# Swith_Matrix.net
KiCad netlist of a schematic drawn in Altium Designer
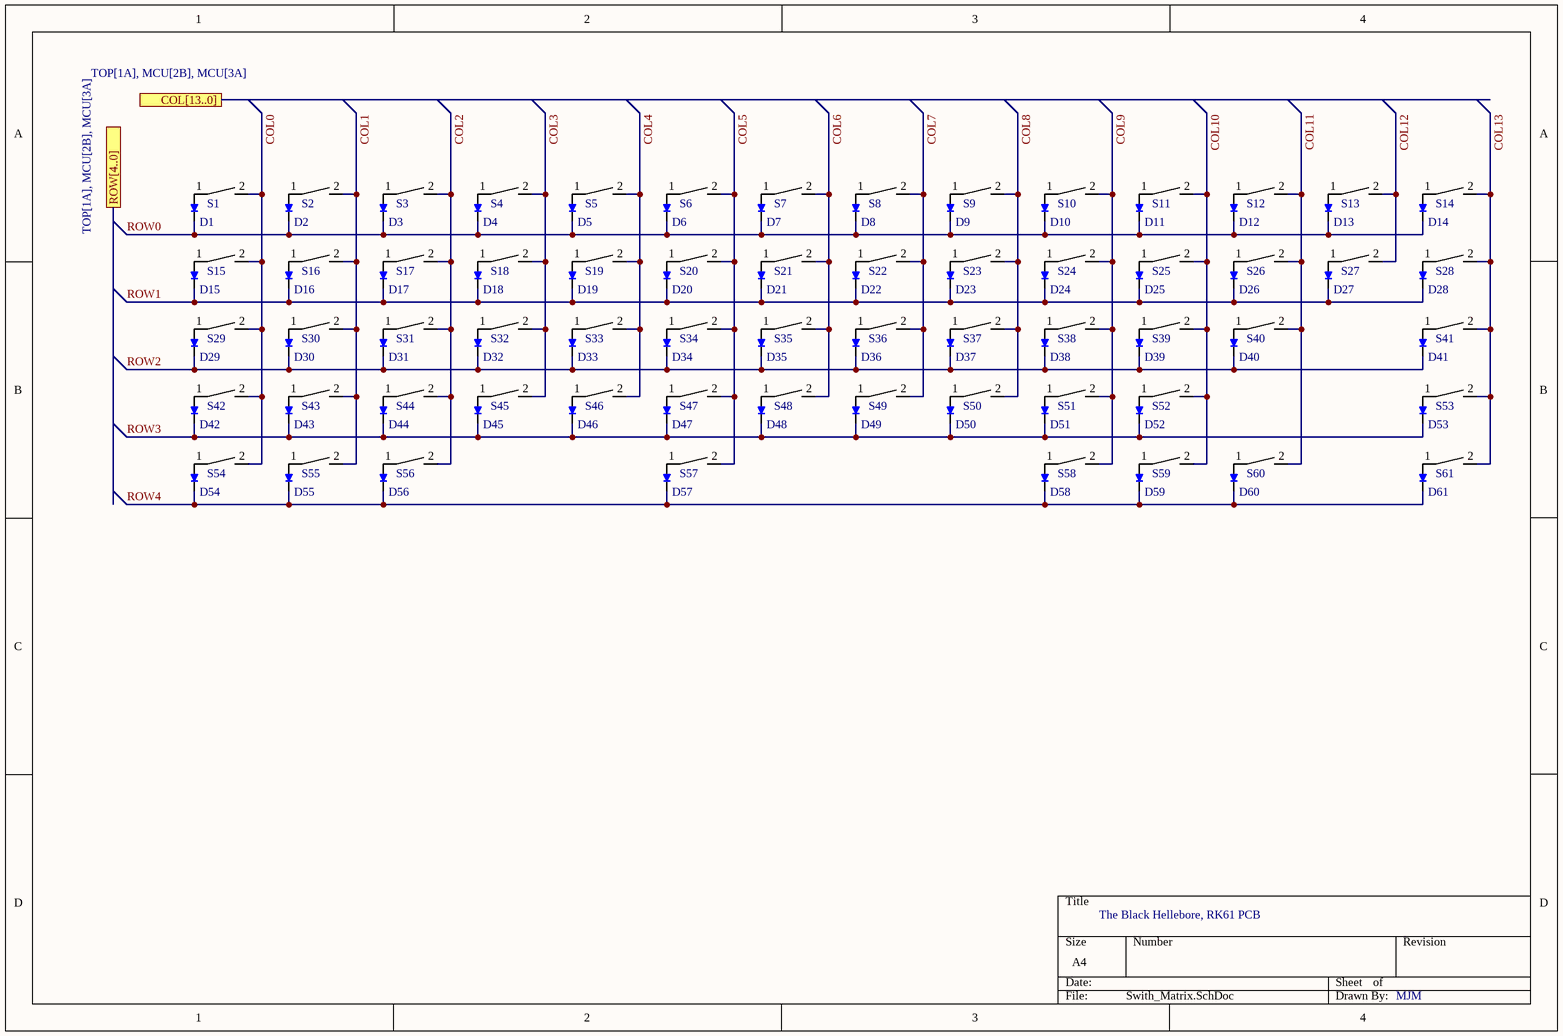
[diagram p0: Swith_Matrix.SchDoc]

(export (version "E")
  (design (tool "Eeschema 10.0.6"))
  (components
    (comp (ref "D1")
      (value "RB520S30T5G")
      (footprint "ONSC-SOD-523-2-502-01_V")
      (description "RB520S30T5G - 30 V 200 mA Surface Mount Schottky Diode - SOD-523")
      (libsource (lib "Microcom Corporation") (part "ONSC-D-K1A2-2"))
    )
    (comp (ref "D2")
      (value "RB520S30T5G")
      (footprint "ONSC-SOD-523-2-502-01_V")
      (description "RB520S30T5G - 30 V 200 mA Surface Mount Schottky Diode - SOD-523")
      (libsource (lib "Microcom Corporation") (part "ONSC-D-K1A2-2"))
    )
    (comp (ref "D3")
      (value "RB520S30T5G")
      (footprint "ONSC-SOD-523-2-502-01_V")
      (description "RB520S30T5G - 30 V 200 mA Surface Mount Schottky Diode - SOD-523")
      (libsource (lib "Microcom Corporation") (part "ONSC-D-K1A2-2"))
    )
    (comp (ref "D4")
      (value "RB520S30T5G")
      (footprint "ONSC-SOD-523-2-502-01_V")
      (description "RB520S30T5G - 30 V 200 mA Surface Mount Schottky Diode - SOD-523")
      (libsource (lib "Microcom Corporation") (part "ONSC-D-K1A2-2"))
    )
    (comp (ref "D5")
      (value "RB520S30T5G")
      (footprint "ONSC-SOD-523-2-502-01_V")
      (description "RB520S30T5G - 30 V 200 mA Surface Mount Schottky Diode - SOD-523")
      (libsource (lib "Microcom Corporation") (part "ONSC-D-K1A2-2"))
    )
    (comp (ref "D6")
      (value "RB520S30T5G")
      (footprint "ONSC-SOD-523-2-502-01_V")
      (description "RB520S30T5G - 30 V 200 mA Surface Mount Schottky Diode - SOD-523")
      (libsource (lib "Microcom Corporation") (part "ONSC-D-K1A2-2"))
    )
    (comp (ref "D7")
      (value "RB520S30T5G")
      (footprint "ONSC-SOD-523-2-502-01_V")
      (description "RB520S30T5G - 30 V 200 mA Surface Mount Schottky Diode - SOD-523")
      (libsource (lib "Microcom Corporation") (part "ONSC-D-K1A2-2"))
    )
    (comp (ref "D8")
      (value "RB520S30T5G")
      (footprint "ONSC-SOD-523-2-502-01_V")
      (description "RB520S30T5G - 30 V 200 mA Surface Mount Schottky Diode - SOD-523")
      (libsource (lib "Microcom Corporation") (part "ONSC-D-K1A2-2"))
    )
    (comp (ref "D9")
      (value "RB520S30T5G")
      (footprint "ONSC-SOD-523-2-502-01_V")
      (description "RB520S30T5G - 30 V 200 mA Surface Mount Schottky Diode - SOD-523")
      (libsource (lib "Microcom Corporation") (part "ONSC-D-K1A2-2"))
    )
    (comp (ref "D10")
      (value "RB520S30T5G")
      (footprint "ONSC-SOD-523-2-502-01_V")
      (description "RB520S30T5G - 30 V 200 mA Surface Mount Schottky Diode - SOD-523")
      (libsource (lib "Microcom Corporation") (part "ONSC-D-K1A2-2"))
    )
    (comp (ref "D11")
      (value "RB520S30T5G")
      (footprint "ONSC-SOD-523-2-502-01_V")
      (description "RB520S30T5G - 30 V 200 mA Surface Mount Schottky Diode - SOD-523")
      (libsource (lib "Microcom Corporation") (part "ONSC-D-K1A2-2"))
    )
    (comp (ref "D12")
      (value "RB520S30T5G")
      (footprint "ONSC-SOD-523-2-502-01_V")
      (description "RB520S30T5G - 30 V 200 mA Surface Mount Schottky Diode - SOD-523")
      (libsource (lib "Microcom Corporation") (part "ONSC-D-K1A2-2"))
    )
    (comp (ref "D13")
      (value "RB520S30T5G")
      (footprint "ONSC-SOD-523-2-502-01_V")
      (description "RB520S30T5G - 30 V 200 mA Surface Mount Schottky Diode - SOD-523")
      (libsource (lib "Microcom Corporation") (part "ONSC-D-K1A2-2"))
    )
    (comp (ref "D14")
      (value "RB520S30T5G")
      (footprint "ONSC-SOD-523-2-502-01_V")
      (description "RB520S30T5G - 30 V 200 mA Surface Mount Schottky Diode - SOD-523")
      (libsource (lib "Microcom Corporation") (part "ONSC-D-K1A2-2"))
    )
    (comp (ref "D15")
      (value "RB520S30T5G")
      (footprint "ONSC-SOD-523-2-502-01_V")
      (description "RB520S30T5G - 30 V 200 mA Surface Mount Schottky Diode - SOD-523")
      (libsource (lib "Microcom Corporation") (part "ONSC-D-K1A2-2"))
    )
    (comp (ref "D16")
      (value "RB520S30T5G")
      (footprint "ONSC-SOD-523-2-502-01_V")
      (description "RB520S30T5G - 30 V 200 mA Surface Mount Schottky Diode - SOD-523")
      (libsource (lib "Microcom Corporation") (part "ONSC-D-K1A2-2"))
    )
    (comp (ref "D17")
      (value "RB520S30T5G")
      (footprint "ONSC-SOD-523-2-502-01_V")
      (description "RB520S30T5G - 30 V 200 mA Surface Mount Schottky Diode - SOD-523")
      (libsource (lib "Microcom Corporation") (part "ONSC-D-K1A2-2"))
    )
    (comp (ref "D18")
      (value "RB520S30T5G")
      (footprint "ONSC-SOD-523-2-502-01_V")
      (description "RB520S30T5G - 30 V 200 mA Surface Mount Schottky Diode - SOD-523")
      (libsource (lib "Microcom Corporation") (part "ONSC-D-K1A2-2"))
    )
    (comp (ref "D19")
      (value "RB520S30T5G")
      (footprint "ONSC-SOD-523-2-502-01_V")
      (description "RB520S30T5G - 30 V 200 mA Surface Mount Schottky Diode - SOD-523")
      (libsource (lib "Microcom Corporation") (part "ONSC-D-K1A2-2"))
    )
    (comp (ref "D20")
      (value "RB520S30T5G")
      (footprint "ONSC-SOD-523-2-502-01_V")
      (description "RB520S30T5G - 30 V 200 mA Surface Mount Schottky Diode - SOD-523")
      (libsource (lib "Microcom Corporation") (part "ONSC-D-K1A2-2"))
    )
    (comp (ref "D21")
      (value "RB520S30T5G")
      (footprint "ONSC-SOD-523-2-502-01_V")
      (description "RB520S30T5G - 30 V 200 mA Surface Mount Schottky Diode - SOD-523")
      (libsource (lib "Microcom Corporation") (part "ONSC-D-K1A2-2"))
    )
    (comp (ref "D22")
      (value "RB520S30T5G")
      (footprint "ONSC-SOD-523-2-502-01_V")
      (description "RB520S30T5G - 30 V 200 mA Surface Mount Schottky Diode - SOD-523")
      (libsource (lib "Microcom Corporation") (part "ONSC-D-K1A2-2"))
    )
    (comp (ref "D23")
      (value "RB520S30T5G")
      (footprint "ONSC-SOD-523-2-502-01_V")
      (description "RB520S30T5G - 30 V 200 mA Surface Mount Schottky Diode - SOD-523")
      (libsource (lib "Microcom Corporation") (part "ONSC-D-K1A2-2"))
    )
    (comp (ref "D24")
      (value "RB520S30T5G")
      (footprint "ONSC-SOD-523-2-502-01_V")
      (description "RB520S30T5G - 30 V 200 mA Surface Mount Schottky Diode - SOD-523")
      (libsource (lib "Microcom Corporation") (part "ONSC-D-K1A2-2"))
    )
    (comp (ref "D25")
      (value "RB520S30T5G")
      (footprint "ONSC-SOD-523-2-502-01_V")
      (description "RB520S30T5G - 30 V 200 mA Surface Mount Schottky Diode - SOD-523")
      (libsource (lib "Microcom Corporation") (part "ONSC-D-K1A2-2"))
    )
    (comp (ref "D26")
      (value "RB520S30T5G")
      (footprint "ONSC-SOD-523-2-502-01_V")
      (description "RB520S30T5G - 30 V 200 mA Surface Mount Schottky Diode - SOD-523")
      (libsource (lib "Microcom Corporation") (part "ONSC-D-K1A2-2"))
    )
    (comp (ref "D27")
      (value "RB520S30T5G")
      (footprint "ONSC-SOD-523-2-502-01_V")
      (description "RB520S30T5G - 30 V 200 mA Surface Mount Schottky Diode - SOD-523")
      (libsource (lib "Microcom Corporation") (part "ONSC-D-K1A2-2"))
    )
    (comp (ref "D28")
      (value "RB520S30T5G")
      (footprint "ONSC-SOD-523-2-502-01_V")
      (description "RB520S30T5G - 30 V 200 mA Surface Mount Schottky Diode - SOD-523")
      (libsource (lib "Microcom Corporation") (part "ONSC-D-K1A2-2"))
    )
    (comp (ref "D29")
      (value "RB520S30T5G")
      (footprint "ONSC-SOD-523-2-502-01_V")
      (description "RB520S30T5G - 30 V 200 mA Surface Mount Schottky Diode - SOD-523")
      (libsource (lib "Microcom Corporation") (part "ONSC-D-K1A2-2"))
    )
    (comp (ref "D30")
      (value "RB520S30T5G")
      (footprint "ONSC-SOD-523-2-502-01_V")
      (description "RB520S30T5G - 30 V 200 mA Surface Mount Schottky Diode - SOD-523")
      (libsource (lib "Microcom Corporation") (part "ONSC-D-K1A2-2"))
    )
    (comp (ref "D31")
      (value "RB520S30T5G")
      (footprint "ONSC-SOD-523-2-502-01_V")
      (description "RB520S30T5G - 30 V 200 mA Surface Mount Schottky Diode - SOD-523")
      (libsource (lib "Microcom Corporation") (part "ONSC-D-K1A2-2"))
    )
    (comp (ref "D32")
      (value "RB520S30T5G")
      (footprint "ONSC-SOD-523-2-502-01_V")
      (description "RB520S30T5G - 30 V 200 mA Surface Mount Schottky Diode - SOD-523")
      (libsource (lib "Microcom Corporation") (part "ONSC-D-K1A2-2"))
    )
    (comp (ref "D33")
      (value "RB520S30T5G")
      (footprint "ONSC-SOD-523-2-502-01_V")
      (description "RB520S30T5G - 30 V 200 mA Surface Mount Schottky Diode - SOD-523")
      (libsource (lib "Microcom Corporation") (part "ONSC-D-K1A2-2"))
    )
    (comp (ref "D34")
      (value "RB520S30T5G")
      (footprint "ONSC-SOD-523-2-502-01_V")
      (description "RB520S30T5G - 30 V 200 mA Surface Mount Schottky Diode - SOD-523")
      (libsource (lib "Microcom Corporation") (part "ONSC-D-K1A2-2"))
    )
    (comp (ref "D35")
      (value "RB520S30T5G")
      (footprint "ONSC-SOD-523-2-502-01_V")
      (description "RB520S30T5G - 30 V 200 mA Surface Mount Schottky Diode - SOD-523")
      (libsource (lib "Microcom Corporation") (part "ONSC-D-K1A2-2"))
    )
    (comp (ref "D36")
      (value "RB520S30T5G")
      (footprint "ONSC-SOD-523-2-502-01_V")
      (description "RB520S30T5G - 30 V 200 mA Surface Mount Schottky Diode - SOD-523")
      (libsource (lib "Microcom Corporation") (part "ONSC-D-K1A2-2"))
    )
    (comp (ref "D37")
      (value "RB520S30T5G")
      (footprint "ONSC-SOD-523-2-502-01_V")
      (description "RB520S30T5G - 30 V 200 mA Surface Mount Schottky Diode - SOD-523")
      (libsource (lib "Microcom Corporation") (part "ONSC-D-K1A2-2"))
    )
    (comp (ref "D38")
      (value "RB520S30T5G")
      (footprint "ONSC-SOD-523-2-502-01_V")
      (description "RB520S30T5G - 30 V 200 mA Surface Mount Schottky Diode - SOD-523")
      (libsource (lib "Microcom Corporation") (part "ONSC-D-K1A2-2"))
    )
    (comp (ref "D39")
      (value "RB520S30T5G")
      (footprint "ONSC-SOD-523-2-502-01_V")
      (description "RB520S30T5G - 30 V 200 mA Surface Mount Schottky Diode - SOD-523")
      (libsource (lib "Microcom Corporation") (part "ONSC-D-K1A2-2"))
    )
    (comp (ref "D40")
      (value "RB520S30T5G")
      (footprint "ONSC-SOD-523-2-502-01_V")
      (description "RB520S30T5G - 30 V 200 mA Surface Mount Schottky Diode - SOD-523")
      (libsource (lib "Microcom Corporation") (part "ONSC-D-K1A2-2"))
    )
    (comp (ref "D41")
      (value "RB520S30T5G")
      (footprint "ONSC-SOD-523-2-502-01_V")
      (description "RB520S30T5G - 30 V 200 mA Surface Mount Schottky Diode - SOD-523")
      (libsource (lib "Microcom Corporation") (part "ONSC-D-K1A2-2"))
    )
    (comp (ref "D42")
      (value "RB520S30T5G")
      (footprint "ONSC-SOD-523-2-502-01_V")
      (description "RB520S30T5G - 30 V 200 mA Surface Mount Schottky Diode - SOD-523")
      (libsource (lib "Microcom Corporation") (part "ONSC-D-K1A2-2"))
    )
    (comp (ref "D43")
      (value "RB520S30T5G")
      (footprint "ONSC-SOD-523-2-502-01_V")
      (description "RB520S30T5G - 30 V 200 mA Surface Mount Schottky Diode - SOD-523")
      (libsource (lib "Microcom Corporation") (part "ONSC-D-K1A2-2"))
    )
    (comp (ref "D44")
      (value "RB520S30T5G")
      (footprint "ONSC-SOD-523-2-502-01_V")
      (description "RB520S30T5G - 30 V 200 mA Surface Mount Schottky Diode - SOD-523")
      (libsource (lib "Microcom Corporation") (part "ONSC-D-K1A2-2"))
    )
    (comp (ref "D45")
      (value "RB520S30T5G")
      (footprint "ONSC-SOD-523-2-502-01_V")
      (description "RB520S30T5G - 30 V 200 mA Surface Mount Schottky Diode - SOD-523")
      (libsource (lib "Microcom Corporation") (part "ONSC-D-K1A2-2"))
    )
    (comp (ref "D46")
      (value "RB520S30T5G")
      (footprint "ONSC-SOD-523-2-502-01_V")
      (description "RB520S30T5G - 30 V 200 mA Surface Mount Schottky Diode - SOD-523")
      (libsource (lib "Microcom Corporation") (part "ONSC-D-K1A2-2"))
    )
    (comp (ref "D47")
      (value "RB520S30T5G")
      (footprint "ONSC-SOD-523-2-502-01_V")
      (description "RB520S30T5G - 30 V 200 mA Surface Mount Schottky Diode - SOD-523")
      (libsource (lib "Microcom Corporation") (part "ONSC-D-K1A2-2"))
    )
    (comp (ref "D48")
      (value "RB520S30T5G")
      (footprint "ONSC-SOD-523-2-502-01_V")
      (description "RB520S30T5G - 30 V 200 mA Surface Mount Schottky Diode - SOD-523")
      (libsource (lib "Microcom Corporation") (part "ONSC-D-K1A2-2"))
    )
    (comp (ref "D49")
      (value "RB520S30T5G")
      (footprint "ONSC-SOD-523-2-502-01_V")
      (description "RB520S30T5G - 30 V 200 mA Surface Mount Schottky Diode - SOD-523")
      (libsource (lib "Microcom Corporation") (part "ONSC-D-K1A2-2"))
    )
    (comp (ref "D50")
      (value "RB520S30T5G")
      (footprint "ONSC-SOD-523-2-502-01_V")
      (description "RB520S30T5G - 30 V 200 mA Surface Mount Schottky Diode - SOD-523")
      (libsource (lib "Microcom Corporation") (part "ONSC-D-K1A2-2"))
    )
    (comp (ref "D51")
      (value "RB520S30T5G")
      (footprint "ONSC-SOD-523-2-502-01_V")
      (description "RB520S30T5G - 30 V 200 mA Surface Mount Schottky Diode - SOD-523")
      (libsource (lib "Microcom Corporation") (part "ONSC-D-K1A2-2"))
    )
    (comp (ref "D52")
      (value "RB520S30T5G")
      (footprint "ONSC-SOD-523-2-502-01_V")
      (description "RB520S30T5G - 30 V 200 mA Surface Mount Schottky Diode - SOD-523")
      (libsource (lib "Microcom Corporation") (part "ONSC-D-K1A2-2"))
    )
    (comp (ref "D53")
      (value "RB520S30T5G")
      (footprint "ONSC-SOD-523-2-502-01_V")
      (description "RB520S30T5G - 30 V 200 mA Surface Mount Schottky Diode - SOD-523")
      (libsource (lib "Microcom Corporation") (part "ONSC-D-K1A2-2"))
    )
    (comp (ref "D54")
      (value "RB520S30T5G")
      (footprint "ONSC-SOD-523-2-502-01_V")
      (description "RB520S30T5G - 30 V 200 mA Surface Mount Schottky Diode - SOD-523")
      (libsource (lib "Microcom Corporation") (part "ONSC-D-K1A2-2"))
    )
    (comp (ref "D55")
      (value "RB520S30T5G")
      (footprint "ONSC-SOD-523-2-502-01_V")
      (description "RB520S30T5G - 30 V 200 mA Surface Mount Schottky Diode - SOD-523")
      (libsource (lib "Microcom Corporation") (part "ONSC-D-K1A2-2"))
    )
    (comp (ref "D56")
      (value "RB520S30T5G")
      (footprint "ONSC-SOD-523-2-502-01_V")
      (description "RB520S30T5G - 30 V 200 mA Surface Mount Schottky Diode - SOD-523")
      (libsource (lib "Microcom Corporation") (part "ONSC-D-K1A2-2"))
    )
    (comp (ref "D57")
      (value "RB520S30T5G")
      (footprint "ONSC-SOD-523-2-502-01_V")
      (description "RB520S30T5G - 30 V 200 mA Surface Mount Schottky Diode - SOD-523")
      (libsource (lib "Microcom Corporation") (part "ONSC-D-K1A2-2"))
    )
    (comp (ref "D58")
      (value "RB520S30T5G")
      (footprint "ONSC-SOD-523-2-502-01_V")
      (description "RB520S30T5G - 30 V 200 mA Surface Mount Schottky Diode - SOD-523")
      (libsource (lib "Microcom Corporation") (part "ONSC-D-K1A2-2"))
    )
    (comp (ref "D59")
      (value "RB520S30T5G")
      (footprint "ONSC-SOD-523-2-502-01_V")
      (description "RB520S30T5G - 30 V 200 mA Surface Mount Schottky Diode - SOD-523")
      (libsource (lib "Microcom Corporation") (part "ONSC-D-K1A2-2"))
    )
    (comp (ref "D60")
      (value "RB520S30T5G")
      (footprint "ONSC-SOD-523-2-502-01_V")
      (description "RB520S30T5G - 30 V 200 mA Surface Mount Schottky Diode - SOD-523")
      (libsource (lib "Microcom Corporation") (part "ONSC-D-K1A2-2"))
    )
    (comp (ref "D61")
      (value "RB520S30T5G")
      (footprint "ONSC-SOD-523-2-502-01_V")
      (description "RB520S30T5G - 30 V 200 mA Surface Mount Schottky Diode - SOD-523")
      (libsource (lib "Microcom Corporation") (part "ONSC-D-K1A2-2"))
    )
    (comp (ref "S1")
      (value "1U-5Pin")
      (footprint "SW_PG151101S11")
      (description "Keyswitch 1U Cherry MX, 5Pin, CPG151101S11-16")
      (fields (field (name "MF") "Kailh") (field (name "MP") "CPG151101S11-16"))
      (libsource (lib "Microcom Corporation") (part "PG151101S11"))
    )
    (comp (ref "S2")
      (value "1U-5Pin")
      (footprint "SW_PG151101S11")
      (description "Keyswitch 1U Cherry MX, 5Pin, CPG151101S11-16")
      (fields (field (name "MF") "Kailh") (field (name "MP") "CPG151101S11-16"))
      (libsource (lib "Microcom Corporation") (part "PG151101S11"))
    )
    (comp (ref "S3")
      (value "1U-5Pin")
      (footprint "SW_PG151101S11")
      (description "Keyswitch 1U Cherry MX, 5Pin, CPG151101S11-16")
      (fields (field (name "MF") "Kailh") (field (name "MP") "CPG151101S11-16"))
      (libsource (lib "Microcom Corporation") (part "PG151101S11"))
    )
    (comp (ref "S4")
      (value "1U-5Pin")
      (footprint "SW_PG151101S11")
      (description "Keyswitch 1U Cherry MX, 5Pin, CPG151101S11-16")
      (fields (field (name "MF") "Kailh") (field (name "MP") "CPG151101S11-16"))
      (libsource (lib "Microcom Corporation") (part "PG151101S11"))
    )
    (comp (ref "S5")
      (value "1U-5Pin")
      (footprint "SW_PG151101S11")
      (description "Keyswitch 1U Cherry MX, 5Pin, CPG151101S11-16")
      (fields (field (name "MF") "Kailh") (field (name "MP") "CPG151101S11-16"))
      (libsource (lib "Microcom Corporation") (part "PG151101S11"))
    )
    (comp (ref "S6")
      (value "1U-5Pin")
      (footprint "SW_PG151101S11")
      (description "Keyswitch 1U Cherry MX, 5Pin, CPG151101S11-16")
      (fields (field (name "MF") "Kailh") (field (name "MP") "CPG151101S11-16"))
      (libsource (lib "Microcom Corporation") (part "PG151101S11"))
    )
    (comp (ref "S7")
      (value "1U-5Pin")
      (footprint "SW_PG151101S11")
      (description "Keyswitch 1U Cherry MX, 5Pin, CPG151101S11-16")
      (fields (field (name "MF") "Kailh") (field (name "MP") "CPG151101S11-16"))
      (libsource (lib "Microcom Corporation") (part "PG151101S11"))
    )
    (comp (ref "S8")
      (value "1U-5Pin")
      (footprint "SW_PG151101S11")
      (description "Keyswitch 1U Cherry MX, 5Pin, CPG151101S11-16")
      (fields (field (name "MF") "Kailh") (field (name "MP") "CPG151101S11-16"))
      (libsource (lib "Microcom Corporation") (part "PG151101S11"))
    )
    (comp (ref "S9")
      (value "1U-5Pin")
      (footprint "SW_PG151101S11")
      (description "Keyswitch 1U Cherry MX, 5Pin, CPG151101S11-16")
      (fields (field (name "MF") "Kailh") (field (name "MP") "CPG151101S11-16"))
      (libsource (lib "Microcom Corporation") (part "PG151101S11"))
    )
    (comp (ref "S10")
      (value "1U-5Pin")
      (footprint "SW_PG151101S11")
      (description "Keyswitch 1U Cherry MX, 5Pin, CPG151101S11-16")
      (fields (field (name "MF") "Kailh") (field (name "MP") "CPG151101S11-16"))
      (libsource (lib "Microcom Corporation") (part "PG151101S11"))
    )
    (comp (ref "S11")
      (value "1U-5Pin")
      (footprint "SW_PG151101S11")
      (description "Keyswitch 1U Cherry MX, 5Pin, CPG151101S11-16")
      (fields (field (name "MF") "Kailh") (field (name "MP") "CPG151101S11-16"))
      (libsource (lib "Microcom Corporation") (part "PG151101S11"))
    )
    (comp (ref "S12")
      (value "1U-5Pin")
      (footprint "SW_PG151101S11")
      (description "Keyswitch 1U Cherry MX, 5Pin, CPG151101S11-16")
      (fields (field (name "MF") "Kailh") (field (name "MP") "CPG151101S11-16"))
      (libsource (lib "Microcom Corporation") (part "PG151101S11"))
    )
    (comp (ref "S13")
      (value "1U-5Pin")
      (footprint "SW_PG151101S11")
      (description "Keyswitch 1U Cherry MX, 5Pin, CPG151101S11-16")
      (fields (field (name "MF") "Kailh") (field (name "MP") "CPG151101S11-16"))
      (libsource (lib "Microcom Corporation") (part "PG151101S11"))
    )
    (comp (ref "S14")
      (value "1U-5Pin")
      (footprint "SW_PG151101S11")
      (description "Keyswitch 1U Cherry MX, 5Pin, CPG151101S11-16")
      (fields (field (name "MF") "Kailh") (field (name "MP") "CPG151101S11-16"))
      (libsource (lib "Microcom Corporation") (part "PG151101S11"))
    )
    (comp (ref "S15")
      (value "1U-5Pin")
      (footprint "SW_PG151101S11")
      (description "Keyswitch 1U Cherry MX, 5Pin, CPG151101S11-16")
      (fields (field (name "MF") "Kailh") (field (name "MP") "CPG151101S11-16"))
      (libsource (lib "Microcom Corporation") (part "PG151101S11"))
    )
    (comp (ref "S16")
      (value "1U-5Pin")
      (footprint "SW_PG151101S11")
      (description "Keyswitch 1U Cherry MX, 5Pin, CPG151101S11-16")
      (fields (field (name "MF") "Kailh") (field (name "MP") "CPG151101S11-16"))
      (libsource (lib "Microcom Corporation") (part "PG151101S11"))
    )
    (comp (ref "S17")
      (value "1U-5Pin")
      (footprint "SW_PG151101S11")
      (description "Keyswitch 1U Cherry MX, 5Pin, CPG151101S11-16")
      (fields (field (name "MF") "Kailh") (field (name "MP") "CPG151101S11-16"))
      (libsource (lib "Microcom Corporation") (part "PG151101S11"))
    )
    (comp (ref "S18")
      (value "1U-5Pin")
      (footprint "SW_PG151101S11")
      (description "Keyswitch 1U Cherry MX, 5Pin, CPG151101S11-16")
      (fields (field (name "MF") "Kailh") (field (name "MP") "CPG151101S11-16"))
      (libsource (lib "Microcom Corporation") (part "PG151101S11"))
    )
    (comp (ref "S19")
      (value "1U-5Pin")
      (footprint "SW_PG151101S11")
      (description "Keyswitch 1U Cherry MX, 5Pin, CPG151101S11-16")
      (fields (field (name "MF") "Kailh") (field (name "MP") "CPG151101S11-16"))
      (libsource (lib "Microcom Corporation") (part "PG151101S11"))
    )
    (comp (ref "S20")
      (value "1U-5Pin")
      (footprint "SW_PG151101S11")
      (description "Keyswitch 1U Cherry MX, 5Pin, CPG151101S11-16")
      (fields (field (name "MF") "Kailh") (field (name "MP") "CPG151101S11-16"))
      (libsource (lib "Microcom Corporation") (part "PG151101S11"))
    )
    (comp (ref "S21")
      (value "1U-5Pin")
      (footprint "SW_PG151101S11")
      (description "Keyswitch 1U Cherry MX, 5Pin, CPG151101S11-16")
      (fields (field (name "MF") "Kailh") (field (name "MP") "CPG151101S11-16"))
      (libsource (lib "Microcom Corporation") (part "PG151101S11"))
    )
    (comp (ref "S22")
      (value "1U-5Pin")
      (footprint "SW_PG151101S11")
      (description "Keyswitch 1U Cherry MX, 5Pin, CPG151101S11-16")
      (fields (field (name "MF") "Kailh") (field (name "MP") "CPG151101S11-16"))
      (libsource (lib "Microcom Corporation") (part "PG151101S11"))
    )
    (comp (ref "S23")
      (value "1U-5Pin")
      (footprint "SW_PG151101S11")
      (description "Keyswitch 1U Cherry MX, 5Pin, CPG151101S11-16")
      (fields (field (name "MF") "Kailh") (field (name "MP") "CPG151101S11-16"))
      (libsource (lib "Microcom Corporation") (part "PG151101S11"))
    )
    (comp (ref "S24")
      (value "1U-5Pin")
      (footprint "SW_PG151101S11")
      (description "Keyswitch 1U Cherry MX, 5Pin, CPG151101S11-16")
      (fields (field (name "MF") "Kailh") (field (name "MP") "CPG151101S11-16"))
      (libsource (lib "Microcom Corporation") (part "PG151101S11"))
    )
    (comp (ref "S25")
      (value "1U-5Pin")
      (footprint "SW_PG151101S11")
      (description "Keyswitch 1U Cherry MX, 5Pin, CPG151101S11-16")
      (fields (field (name "MF") "Kailh") (field (name "MP") "CPG151101S11-16"))
      (libsource (lib "Microcom Corporation") (part "PG151101S11"))
    )
    (comp (ref "S26")
      (value "1U-5Pin")
      (footprint "SW_PG151101S11")
      (description "Keyswitch 1U Cherry MX, 5Pin, CPG151101S11-16")
      (fields (field (name "MF") "Kailh") (field (name "MP") "CPG151101S11-16"))
      (libsource (lib "Microcom Corporation") (part "PG151101S11"))
    )
    (comp (ref "S27")
      (value "1U-5Pin")
      (footprint "SW_PG151101S11")
      (description "Keyswitch 1U Cherry MX, 5Pin, CPG151101S11-16")
      (fields (field (name "MF") "Kailh") (field (name "MP") "CPG151101S11-16"))
      (libsource (lib "Microcom Corporation") (part "PG151101S11"))
    )
    (comp (ref "S28")
      (value "1U-5Pin")
      (footprint "SW_PG151101S11")
      (description "Keyswitch 1U Cherry MX, 5Pin, CPG151101S11-16")
      (fields (field (name "MF") "Kailh") (field (name "MP") "CPG151101S11-16"))
      (libsource (lib "Microcom Corporation") (part "PG151101S11"))
    )
    (comp (ref "S29")
      (value "1U-5Pin")
      (footprint "SW_PG151101S11")
      (description "Keyswitch 1U Cherry MX, 5Pin, CPG151101S11-16")
      (fields (field (name "MF") "Kailh") (field (name "MP") "CPG151101S11-16"))
      (libsource (lib "Microcom Corporation") (part "PG151101S11"))
    )
    (comp (ref "S30")
      (value "1U-5Pin")
      (footprint "SW_PG151101S11")
      (description "Keyswitch 1U Cherry MX, 5Pin, CPG151101S11-16")
      (fields (field (name "MF") "Kailh") (field (name "MP") "CPG151101S11-16"))
      (libsource (lib "Microcom Corporation") (part "PG151101S11"))
    )
    (comp (ref "S31")
      (value "1U-5Pin")
      (footprint "SW_PG151101S11")
      (description "Keyswitch 1U Cherry MX, 5Pin, CPG151101S11-16")
      (fields (field (name "MF") "Kailh") (field (name "MP") "CPG151101S11-16"))
      (libsource (lib "Microcom Corporation") (part "PG151101S11"))
    )
    (comp (ref "S32")
      (value "1U-5Pin")
      (footprint "SW_PG151101S11")
      (description "Keyswitch 1U Cherry MX, 5Pin, CPG151101S11-16")
      (fields (field (name "MF") "Kailh") (field (name "MP") "CPG151101S11-16"))
      (libsource (lib "Microcom Corporation") (part "PG151101S11"))
    )
    (comp (ref "S33")
      (value "1U-5Pin")
      (footprint "SW_PG151101S11")
      (description "Keyswitch 1U Cherry MX, 5Pin, CPG151101S11-16")
      (fields (field (name "MF") "Kailh") (field (name "MP") "CPG151101S11-16"))
      (libsource (lib "Microcom Corporation") (part "PG151101S11"))
    )
    (comp (ref "S34")
      (value "1U-5Pin")
      (footprint "SW_PG151101S11")
      (description "Keyswitch 1U Cherry MX, 5Pin, CPG151101S11-16")
      (fields (field (name "MF") "Kailh") (field (name "MP") "CPG151101S11-16"))
      (libsource (lib "Microcom Corporation") (part "PG151101S11"))
    )
    (comp (ref "S35")
      (value "1U-5Pin")
      (footprint "SW_PG151101S11")
      (description "Keyswitch 1U Cherry MX, 5Pin, CPG151101S11-16")
      (fields (field (name "MF") "Kailh") (field (name "MP") "CPG151101S11-16"))
      (libsource (lib "Microcom Corporation") (part "PG151101S11"))
    )
    (comp (ref "S36")
      (value "1U-5Pin")
      (footprint "SW_PG151101S11")
      (description "Keyswitch 1U Cherry MX, 5Pin, CPG151101S11-16")
      (fields (field (name "MF") "Kailh") (field (name "MP") "CPG151101S11-16"))
      (libsource (lib "Microcom Corporation") (part "PG151101S11"))
    )
    (comp (ref "S37")
      (value "1U-5Pin")
      (footprint "SW_PG151101S11")
      (description "Keyswitch 1U Cherry MX, 5Pin, CPG151101S11-16")
      (fields (field (name "MF") "Kailh") (field (name "MP") "CPG151101S11-16"))
      (libsource (lib "Microcom Corporation") (part "PG151101S11"))
    )
    (comp (ref "S38")
      (value "1U-5Pin")
      (footprint "SW_PG151101S11")
      (description "Keyswitch 1U Cherry MX, 5Pin, CPG151101S11-16")
      (fields (field (name "MF") "Kailh") (field (name "MP") "CPG151101S11-16"))
      (libsource (lib "Microcom Corporation") (part "PG151101S11"))
    )
    (comp (ref "S39")
      (value "1U-5Pin")
      (footprint "SW_PG151101S11")
      (description "Keyswitch 1U Cherry MX, 5Pin, CPG151101S11-16")
      (fields (field (name "MF") "Kailh") (field (name "MP") "CPG151101S11-16"))
      (libsource (lib "Microcom Corporation") (part "PG151101S11"))
    )
    (comp (ref "S40")
      (value "1U-5Pin")
      (footprint "SW_PG151101S11")
      (description "Keyswitch 1U Cherry MX, 5Pin, CPG151101S11-16")
      (fields (field (name "MF") "Kailh") (field (name "MP") "CPG151101S11-16"))
      (libsource (lib "Microcom Corporation") (part "PG151101S11"))
    )
    (comp (ref "S41")
      (value "1U-5Pin")
      (footprint "SW_PG151101S11")
      (description "Keyswitch 1U Cherry MX, 5Pin, CPG151101S11-16")
      (fields (field (name "MF") "Kailh") (field (name "MP") "CPG151101S11-16"))
      (libsource (lib "Microcom Corporation") (part "PG151101S11"))
    )
    (comp (ref "S42")
      (value "1U-5Pin")
      (footprint "SW_PG151101S11")
      (description "Keyswitch 1U Cherry MX, 5Pin, CPG151101S11-16")
      (fields (field (name "MF") "Kailh") (field (name "MP") "CPG151101S11-16"))
      (libsource (lib "Microcom Corporation") (part "PG151101S11"))
    )
    (comp (ref "S43")
      (value "1U-5Pin")
      (footprint "SW_PG151101S11")
      (description "Keyswitch 1U Cherry MX, 5Pin, CPG151101S11-16")
      (fields (field (name "MF") "Kailh") (field (name "MP") "CPG151101S11-16"))
      (libsource (lib "Microcom Corporation") (part "PG151101S11"))
    )
    (comp (ref "S44")
      (value "1U-5Pin")
      (footprint "SW_PG151101S11")
      (description "Keyswitch 1U Cherry MX, 5Pin, CPG151101S11-16")
      (fields (field (name "MF") "Kailh") (field (name "MP") "CPG151101S11-16"))
      (libsource (lib "Microcom Corporation") (part "PG151101S11"))
    )
    (comp (ref "S45")
      (value "1U-5Pin")
      (footprint "SW_PG151101S11")
      (description "Keyswitch 1U Cherry MX, 5Pin, CPG151101S11-16")
      (fields (field (name "MF") "Kailh") (field (name "MP") "CPG151101S11-16"))
      (libsource (lib "Microcom Corporation") (part "PG151101S11"))
    )
    (comp (ref "S46")
      (value "1U-5Pin")
      (footprint "SW_PG151101S11")
      (description "Keyswitch 1U Cherry MX, 5Pin, CPG151101S11-16")
      (fields (field (name "MF") "Kailh") (field (name "MP") "CPG151101S11-16"))
      (libsource (lib "Microcom Corporation") (part "PG151101S11"))
    )
    (comp (ref "S47")
      (value "1U-5Pin")
      (footprint "SW_PG151101S11")
      (description "Keyswitch 1U Cherry MX, 5Pin, CPG151101S11-16")
      (fields (field (name "MF") "Kailh") (field (name "MP") "CPG151101S11-16"))
      (libsource (lib "Microcom Corporation") (part "PG151101S11"))
    )
    (comp (ref "S48")
      (value "1U-5Pin")
      (footprint "SW_PG151101S11")
      (description "Keyswitch 1U Cherry MX, 5Pin, CPG151101S11-16")
      (fields (field (name "MF") "Kailh") (field (name "MP") "CPG151101S11-16"))
      (libsource (lib "Microcom Corporation") (part "PG151101S11"))
    )
    (comp (ref "S49")
      (value "1U-5Pin")
      (footprint "SW_PG151101S11")
      (description "Keyswitch 1U Cherry MX, 5Pin, CPG151101S11-16")
      (fields (field (name "MF") "Kailh") (field (name "MP") "CPG151101S11-16"))
      (libsource (lib "Microcom Corporation") (part "PG151101S11"))
    )
    (comp (ref "S50")
      (value "1U-5Pin")
      (footprint "SW_PG151101S11")
      (description "Keyswitch 1U Cherry MX, 5Pin, CPG151101S11-16")
      (fields (field (name "MF") "Kailh") (field (name "MP") "CPG151101S11-16"))
      (libsource (lib "Microcom Corporation") (part "PG151101S11"))
    )
    (comp (ref "S51")
      (value "1U-5Pin")
      (footprint "SW_PG151101S11")
      (description "Keyswitch 1U Cherry MX, 5Pin, CPG151101S11-16")
      (fields (field (name "MF") "Kailh") (field (name "MP") "CPG151101S11-16"))
      (libsource (lib "Microcom Corporation") (part "PG151101S11"))
    )
    (comp (ref "S52")
      (value "1U-5Pin")
      (footprint "SW_PG151101S11")
      (description "Keyswitch 1U Cherry MX, 5Pin, CPG151101S11-16")
      (fields (field (name "MF") "Kailh") (field (name "MP") "CPG151101S11-16"))
      (libsource (lib "Microcom Corporation") (part "PG151101S11"))
    )
    (comp (ref "S53")
      (value "1U-5Pin")
      (footprint "SW_PG151101S11")
      (description "Keyswitch 1U Cherry MX, 5Pin, CPG151101S11-16")
      (fields (field (name "MF") "Kailh") (field (name "MP") "CPG151101S11-16"))
      (libsource (lib "Microcom Corporation") (part "PG151101S11"))
    )
    (comp (ref "S54")
      (value "1U-5Pin")
      (footprint "SW_PG151101S11")
      (description "Keyswitch 1U Cherry MX, 5Pin, CPG151101S11-16")
      (fields (field (name "MF") "Kailh") (field (name "MP") "CPG151101S11-16"))
      (libsource (lib "Microcom Corporation") (part "PG151101S11"))
    )
    (comp (ref "S55")
      (value "1U-5Pin")
      (footprint "SW_PG151101S11")
      (description "Keyswitch 1U Cherry MX, 5Pin, CPG151101S11-16")
      (fields (field (name "MF") "Kailh") (field (name "MP") "CPG151101S11-16"))
      (libsource (lib "Microcom Corporation") (part "PG151101S11"))
    )
    (comp (ref "S56")
      (value "1U-5Pin")
      (footprint "SW_PG151101S11")
      (description "Keyswitch 1U Cherry MX, 5Pin, CPG151101S11-16")
      (fields (field (name "MF") "Kailh") (field (name "MP") "CPG151101S11-16"))
      (libsource (lib "Microcom Corporation") (part "PG151101S11"))
    )
    (comp (ref "S57")
      (value "1U-5Pin")
      (footprint "SW_PG151101S11")
      (description "Keyswitch 1U Cherry MX, 5Pin, CPG151101S11-16")
      (fields (field (name "MF") "Kailh") (field (name "MP") "CPG151101S11-16"))
      (libsource (lib "Microcom Corporation") (part "PG151101S11"))
    )
    (comp (ref "S58")
      (value "1U-5Pin")
      (footprint "SW_PG151101S11")
      (description "Keyswitch 1U Cherry MX, 5Pin, CPG151101S11-16")
      (fields (field (name "MF") "Kailh") (field (name "MP") "CPG151101S11-16"))
      (libsource (lib "Microcom Corporation") (part "PG151101S11"))
    )
    (comp (ref "S59")
      (value "1U-5Pin")
      (footprint "SW_PG151101S11")
      (description "Keyswitch 1U Cherry MX, 5Pin, CPG151101S11-16")
      (fields (field (name "MF") "Kailh") (field (name "MP") "CPG151101S11-16"))
      (libsource (lib "Microcom Corporation") (part "PG151101S11"))
    )
    (comp (ref "S60")
      (value "1U-5Pin")
      (footprint "SW_PG151101S11")
      (description "Keyswitch 1U Cherry MX, 5Pin, CPG151101S11-16")
      (fields (field (name "MF") "Kailh") (field (name "MP") "CPG151101S11-16"))
      (libsource (lib "Microcom Corporation") (part "PG151101S11"))
    )
    (comp (ref "S61")
      (value "1U-5Pin")
      (footprint "SW_PG151101S11")
      (description "Keyswitch 1U Cherry MX, 5Pin, CPG151101S11-16")
      (fields (field (name "MF") "Kailh") (field (name "MP") "CPG151101S11-16"))
      (libsource (lib "Microcom Corporation") (part "PG151101S11"))
    )
  )
  (nets
    (net (code "1") (name "/COL0") (class "Default")
      (node (ref "S1") (pin "2") (pinfunction "2_2") (pintype "passive"))
      (node (ref "S15") (pin "2") (pinfunction "2_2") (pintype "passive"))
      (node (ref "S29") (pin "2") (pinfunction "2_2") (pintype "passive"))
      (node (ref "S42") (pin "2") (pinfunction "2_2") (pintype "passive"))
      (node (ref "S54") (pin "2") (pinfunction "2_2") (pintype "passive"))
    )
    (net (code "2") (name "/COL1") (class "Default")
      (node (ref "S16") (pin "2") (pinfunction "2_2") (pintype "passive"))
      (node (ref "S2") (pin "2") (pinfunction "2_2") (pintype "passive"))
      (node (ref "S30") (pin "2") (pinfunction "2_2") (pintype "passive"))
      (node (ref "S43") (pin "2") (pinfunction "2_2") (pintype "passive"))
      (node (ref "S55") (pin "2") (pinfunction "2_2") (pintype "passive"))
    )
    (net (code "3") (name "/COL2") (class "Default")
      (node (ref "S17") (pin "2") (pinfunction "2_2") (pintype "passive"))
      (node (ref "S3") (pin "2") (pinfunction "2_2") (pintype "passive"))
      (node (ref "S31") (pin "2") (pinfunction "2_2") (pintype "passive"))
      (node (ref "S44") (pin "2") (pinfunction "2_2") (pintype "passive"))
      (node (ref "S56") (pin "2") (pinfunction "2_2") (pintype "passive"))
    )
    (net (code "4") (name "/COL3") (class "Default")
      (node (ref "S18") (pin "2") (pinfunction "2_2") (pintype "passive"))
      (node (ref "S32") (pin "2") (pinfunction "2_2") (pintype "passive"))
      (node (ref "S4") (pin "2") (pinfunction "2_2") (pintype "passive"))
      (node (ref "S45") (pin "2") (pinfunction "2_2") (pintype "passive"))
    )
    (net (code "5") (name "/COL4") (class "Default")
      (node (ref "S19") (pin "2") (pinfunction "2_2") (pintype "passive"))
      (node (ref "S33") (pin "2") (pinfunction "2_2") (pintype "passive"))
      (node (ref "S46") (pin "2") (pinfunction "2_2") (pintype "passive"))
      (node (ref "S5") (pin "2") (pinfunction "2_2") (pintype "passive"))
    )
    (net (code "6") (name "/COL5") (class "Default")
      (node (ref "S20") (pin "2") (pinfunction "2_2") (pintype "passive"))
      (node (ref "S34") (pin "2") (pinfunction "2_2") (pintype "passive"))
      (node (ref "S47") (pin "2") (pinfunction "2_2") (pintype "passive"))
      (node (ref "S57") (pin "2") (pinfunction "2_2") (pintype "passive"))
      (node (ref "S6") (pin "2") (pinfunction "2_2") (pintype "passive"))
    )
    (net (code "7") (name "/COL6") (class "Default")
      (node (ref "S21") (pin "2") (pinfunction "2_2") (pintype "passive"))
      (node (ref "S35") (pin "2") (pinfunction "2_2") (pintype "passive"))
      (node (ref "S48") (pin "2") (pinfunction "2_2") (pintype "passive"))
      (node (ref "S7") (pin "2") (pinfunction "2_2") (pintype "passive"))
    )
    (net (code "8") (name "/COL7") (class "Default")
      (node (ref "S22") (pin "2") (pinfunction "2_2") (pintype "passive"))
      (node (ref "S36") (pin "2") (pinfunction "2_2") (pintype "passive"))
      (node (ref "S49") (pin "2") (pinfunction "2_2") (pintype "passive"))
      (node (ref "S8") (pin "2") (pinfunction "2_2") (pintype "passive"))
    )
    (net (code "9") (name "/COL8") (class "Default")
      (node (ref "S23") (pin "2") (pinfunction "2_2") (pintype "passive"))
      (node (ref "S37") (pin "2") (pinfunction "2_2") (pintype "passive"))
      (node (ref "S50") (pin "2") (pinfunction "2_2") (pintype "passive"))
      (node (ref "S9") (pin "2") (pinfunction "2_2") (pintype "passive"))
    )
    (net (code "10") (name "/COL9") (class "Default")
      (node (ref "S10") (pin "2") (pinfunction "2_2") (pintype "passive"))
      (node (ref "S24") (pin "2") (pinfunction "2_2") (pintype "passive"))
      (node (ref "S38") (pin "2") (pinfunction "2_2") (pintype "passive"))
      (node (ref "S51") (pin "2") (pinfunction "2_2") (pintype "passive"))
      (node (ref "S58") (pin "2") (pinfunction "2_2") (pintype "passive"))
    )
    (net (code "11") (name "/COL10") (class "Default")
      (node (ref "S11") (pin "2") (pinfunction "2_2") (pintype "passive"))
      (node (ref "S25") (pin "2") (pinfunction "2_2") (pintype "passive"))
      (node (ref "S39") (pin "2") (pinfunction "2_2") (pintype "passive"))
      (node (ref "S52") (pin "2") (pinfunction "2_2") (pintype "passive"))
      (node (ref "S59") (pin "2") (pinfunction "2_2") (pintype "passive"))
    )
    (net (code "12") (name "/COL11") (class "Default")
      (node (ref "S12") (pin "2") (pinfunction "2_2") (pintype "passive"))
      (node (ref "S26") (pin "2") (pinfunction "2_2") (pintype "passive"))
      (node (ref "S40") (pin "2") (pinfunction "2_2") (pintype "passive"))
      (node (ref "S60") (pin "2") (pinfunction "2_2") (pintype "passive"))
    )
    (net (code "13") (name "/COL12") (class "Default")
      (node (ref "S13") (pin "2") (pinfunction "2_2") (pintype "passive"))
      (node (ref "S27") (pin "2") (pinfunction "2_2") (pintype "passive"))
    )
    (net (code "14") (name "/COL13") (class "Default")
      (node (ref "S14") (pin "2") (pinfunction "2_2") (pintype "passive"))
      (node (ref "S28") (pin "2") (pinfunction "2_2") (pintype "passive"))
      (node (ref "S41") (pin "2") (pinfunction "2_2") (pintype "passive"))
      (node (ref "S53") (pin "2") (pinfunction "2_2") (pintype "passive"))
      (node (ref "S61") (pin "2") (pinfunction "2_2") (pintype "passive"))
    )
    (net (code "16") (name "/ROW0") (class "Default")
      (node (ref "D1") (pin "1") (pinfunction "K_1") (pintype "passive"))
      (node (ref "D10") (pin "1") (pinfunction "K_1") (pintype "passive"))
      (node (ref "D11") (pin "1") (pinfunction "K_1") (pintype "passive"))
      (node (ref "D12") (pin "1") (pinfunction "K_1") (pintype "passive"))
      (node (ref "D13") (pin "1") (pinfunction "K_1") (pintype "passive"))
      (node (ref "D14") (pin "1") (pinfunction "K_1") (pintype "passive"))
      (node (ref "D2") (pin "1") (pinfunction "K_1") (pintype "passive"))
      (node (ref "D3") (pin "1") (pinfunction "K_1") (pintype "passive"))
      (node (ref "D4") (pin "1") (pinfunction "K_1") (pintype "passive"))
      (node (ref "D5") (pin "1") (pinfunction "K_1") (pintype "passive"))
      (node (ref "D6") (pin "1") (pinfunction "K_1") (pintype "passive"))
      (node (ref "D7") (pin "1") (pinfunction "K_1") (pintype "passive"))
      (node (ref "D8") (pin "1") (pinfunction "K_1") (pintype "passive"))
      (node (ref "D9") (pin "1") (pinfunction "K_1") (pintype "passive"))
    )
    (net (code "17") (name "/ROW1") (class "Default")
      (node (ref "D15") (pin "1") (pinfunction "K_1") (pintype "passive"))
      (node (ref "D16") (pin "1") (pinfunction "K_1") (pintype "passive"))
      (node (ref "D17") (pin "1") (pinfunction "K_1") (pintype "passive"))
      (node (ref "D18") (pin "1") (pinfunction "K_1") (pintype "passive"))
      (node (ref "D19") (pin "1") (pinfunction "K_1") (pintype "passive"))
      (node (ref "D20") (pin "1") (pinfunction "K_1") (pintype "passive"))
      (node (ref "D21") (pin "1") (pinfunction "K_1") (pintype "passive"))
      (node (ref "D22") (pin "1") (pinfunction "K_1") (pintype "passive"))
      (node (ref "D23") (pin "1") (pinfunction "K_1") (pintype "passive"))
      (node (ref "D24") (pin "1") (pinfunction "K_1") (pintype "passive"))
      (node (ref "D25") (pin "1") (pinfunction "K_1") (pintype "passive"))
      (node (ref "D26") (pin "1") (pinfunction "K_1") (pintype "passive"))
      (node (ref "D27") (pin "1") (pinfunction "K_1") (pintype "passive"))
      (node (ref "D28") (pin "1") (pinfunction "K_1") (pintype "passive"))
    )
    (net (code "18") (name "/ROW2") (class "Default")
      (node (ref "D29") (pin "1") (pinfunction "K_1") (pintype "passive"))
      (node (ref "D30") (pin "1") (pinfunction "K_1") (pintype "passive"))
      (node (ref "D31") (pin "1") (pinfunction "K_1") (pintype "passive"))
      (node (ref "D32") (pin "1") (pinfunction "K_1") (pintype "passive"))
      (node (ref "D33") (pin "1") (pinfunction "K_1") (pintype "passive"))
      (node (ref "D34") (pin "1") (pinfunction "K_1") (pintype "passive"))
      (node (ref "D35") (pin "1") (pinfunction "K_1") (pintype "passive"))
      (node (ref "D36") (pin "1") (pinfunction "K_1") (pintype "passive"))
      (node (ref "D37") (pin "1") (pinfunction "K_1") (pintype "passive"))
      (node (ref "D38") (pin "1") (pinfunction "K_1") (pintype "passive"))
      (node (ref "D39") (pin "1") (pinfunction "K_1") (pintype "passive"))
      (node (ref "D40") (pin "1") (pinfunction "K_1") (pintype "passive"))
      (node (ref "D41") (pin "1") (pinfunction "K_1") (pintype "passive"))
    )
    (net (code "19") (name "/ROW3") (class "Default")
      (node (ref "D42") (pin "1") (pinfunction "K_1") (pintype "passive"))
      (node (ref "D43") (pin "1") (pinfunction "K_1") (pintype "passive"))
      (node (ref "D44") (pin "1") (pinfunction "K_1") (pintype "passive"))
      (node (ref "D45") (pin "1") (pinfunction "K_1") (pintype "passive"))
      (node (ref "D46") (pin "1") (pinfunction "K_1") (pintype "passive"))
      (node (ref "D47") (pin "1") (pinfunction "K_1") (pintype "passive"))
      (node (ref "D48") (pin "1") (pinfunction "K_1") (pintype "passive"))
      (node (ref "D49") (pin "1") (pinfunction "K_1") (pintype "passive"))
      (node (ref "D50") (pin "1") (pinfunction "K_1") (pintype "passive"))
      (node (ref "D51") (pin "1") (pinfunction "K_1") (pintype "passive"))
      (node (ref "D52") (pin "1") (pinfunction "K_1") (pintype "passive"))
      (node (ref "D53") (pin "1") (pinfunction "K_1") (pintype "passive"))
    )
    (net (code "20") (name "/ROW4") (class "Default")
      (node (ref "D54") (pin "1") (pinfunction "K_1") (pintype "passive"))
      (node (ref "D55") (pin "1") (pinfunction "K_1") (pintype "passive"))
      (node (ref "D56") (pin "1") (pinfunction "K_1") (pintype "passive"))
      (node (ref "D57") (pin "1") (pinfunction "K_1") (pintype "passive"))
      (node (ref "D58") (pin "1") (pinfunction "K_1") (pintype "passive"))
      (node (ref "D59") (pin "1") (pinfunction "K_1") (pintype "passive"))
      (node (ref "D60") (pin "1") (pinfunction "K_1") (pintype "passive"))
      (node (ref "D61") (pin "1") (pinfunction "K_1") (pintype "passive"))
    )
    (net (code "22") (name "Net-(D1-A)") (class "Default")
      (node (ref "D1") (pin "2") (pinfunction "A_2") (pintype "passive"))
      (node (ref "S1") (pin "1") (pinfunction "1_1") (pintype "passive"))
    )
    (net (code "23") (name "Net-(D2-A)") (class "Default")
      (node (ref "D2") (pin "2") (pinfunction "A_2") (pintype "passive"))
      (node (ref "S2") (pin "1") (pinfunction "1_1") (pintype "passive"))
    )
    (net (code "24") (name "Net-(D3-A)") (class "Default")
      (node (ref "D3") (pin "2") (pinfunction "A_2") (pintype "passive"))
      (node (ref "S3") (pin "1") (pinfunction "1_1") (pintype "passive"))
    )
    (net (code "25") (name "Net-(D4-A)") (class "Default")
      (node (ref "D4") (pin "2") (pinfunction "A_2") (pintype "passive"))
      (node (ref "S4") (pin "1") (pinfunction "1_1") (pintype "passive"))
    )
    (net (code "26") (name "Net-(D5-A)") (class "Default")
      (node (ref "D5") (pin "2") (pinfunction "A_2") (pintype "passive"))
      (node (ref "S5") (pin "1") (pinfunction "1_1") (pintype "passive"))
    )
    (net (code "27") (name "Net-(D6-A)") (class "Default")
      (node (ref "D6") (pin "2") (pinfunction "A_2") (pintype "passive"))
      (node (ref "S6") (pin "1") (pinfunction "1_1") (pintype "passive"))
    )
    (net (code "28") (name "Net-(D7-A)") (class "Default")
      (node (ref "D7") (pin "2") (pinfunction "A_2") (pintype "passive"))
      (node (ref "S7") (pin "1") (pinfunction "1_1") (pintype "passive"))
    )
    (net (code "29") (name "Net-(D8-A)") (class "Default")
      (node (ref "D8") (pin "2") (pinfunction "A_2") (pintype "passive"))
      (node (ref "S8") (pin "1") (pinfunction "1_1") (pintype "passive"))
    )
    (net (code "30") (name "Net-(D9-A)") (class "Default")
      (node (ref "D9") (pin "2") (pinfunction "A_2") (pintype "passive"))
      (node (ref "S9") (pin "1") (pinfunction "1_1") (pintype "passive"))
    )
    (net (code "31") (name "Net-(D10-A)") (class "Default")
      (node (ref "D10") (pin "2") (pinfunction "A_2") (pintype "passive"))
      (node (ref "S10") (pin "1") (pinfunction "1_1") (pintype "passive"))
    )
    (net (code "32") (name "Net-(D11-A)") (class "Default")
      (node (ref "D11") (pin "2") (pinfunction "A_2") (pintype "passive"))
      (node (ref "S11") (pin "1") (pinfunction "1_1") (pintype "passive"))
    )
    (net (code "33") (name "Net-(D12-A)") (class "Default")
      (node (ref "D12") (pin "2") (pinfunction "A_2") (pintype "passive"))
      (node (ref "S12") (pin "1") (pinfunction "1_1") (pintype "passive"))
    )
    (net (code "34") (name "Net-(D13-A)") (class "Default")
      (node (ref "D13") (pin "2") (pinfunction "A_2") (pintype "passive"))
      (node (ref "S13") (pin "1") (pinfunction "1_1") (pintype "passive"))
    )
    (net (code "35") (name "Net-(D14-A)") (class "Default")
      (node (ref "D14") (pin "2") (pinfunction "A_2") (pintype "passive"))
      (node (ref "S14") (pin "1") (pinfunction "1_1") (pintype "passive"))
    )
    (net (code "36") (name "Net-(D15-A)") (class "Default")
      (node (ref "D15") (pin "2") (pinfunction "A_2") (pintype "passive"))
      (node (ref "S15") (pin "1") (pinfunction "1_1") (pintype "passive"))
    )
    (net (code "37") (name "Net-(D16-A)") (class "Default")
      (node (ref "D16") (pin "2") (pinfunction "A_2") (pintype "passive"))
      (node (ref "S16") (pin "1") (pinfunction "1_1") (pintype "passive"))
    )
    (net (code "38") (name "Net-(D17-A)") (class "Default")
      (node (ref "D17") (pin "2") (pinfunction "A_2") (pintype "passive"))
      (node (ref "S17") (pin "1") (pinfunction "1_1") (pintype "passive"))
    )
    (net (code "39") (name "Net-(D18-A)") (class "Default")
      (node (ref "D18") (pin "2") (pinfunction "A_2") (pintype "passive"))
      (node (ref "S18") (pin "1") (pinfunction "1_1") (pintype "passive"))
    )
    (net (code "40") (name "Net-(D19-A)") (class "Default")
      (node (ref "D19") (pin "2") (pinfunction "A_2") (pintype "passive"))
      (node (ref "S19") (pin "1") (pinfunction "1_1") (pintype "passive"))
    )
    (net (code "41") (name "Net-(D20-A)") (class "Default")
      (node (ref "D20") (pin "2") (pinfunction "A_2") (pintype "passive"))
      (node (ref "S20") (pin "1") (pinfunction "1_1") (pintype "passive"))
    )
    (net (code "42") (name "Net-(D21-A)") (class "Default")
      (node (ref "D21") (pin "2") (pinfunction "A_2") (pintype "passive"))
      (node (ref "S21") (pin "1") (pinfunction "1_1") (pintype "passive"))
    )
    (net (code "43") (name "Net-(D22-A)") (class "Default")
      (node (ref "D22") (pin "2") (pinfunction "A_2") (pintype "passive"))
      (node (ref "S22") (pin "1") (pinfunction "1_1") (pintype "passive"))
    )
    (net (code "44") (name "Net-(D23-A)") (class "Default")
      (node (ref "D23") (pin "2") (pinfunction "A_2") (pintype "passive"))
      (node (ref "S23") (pin "1") (pinfunction "1_1") (pintype "passive"))
    )
    (net (code "45") (name "Net-(D24-A)") (class "Default")
      (node (ref "D24") (pin "2") (pinfunction "A_2") (pintype "passive"))
      (node (ref "S24") (pin "1") (pinfunction "1_1") (pintype "passive"))
    )
    (net (code "46") (name "Net-(D25-A)") (class "Default")
      (node (ref "D25") (pin "2") (pinfunction "A_2") (pintype "passive"))
      (node (ref "S25") (pin "1") (pinfunction "1_1") (pintype "passive"))
    )
    (net (code "47") (name "Net-(D26-A)") (class "Default")
      (node (ref "D26") (pin "2") (pinfunction "A_2") (pintype "passive"))
      (node (ref "S26") (pin "1") (pinfunction "1_1") (pintype "passive"))
    )
    (net (code "48") (name "Net-(D27-A)") (class "Default")
      (node (ref "D27") (pin "2") (pinfunction "A_2") (pintype "passive"))
      (node (ref "S27") (pin "1") (pinfunction "1_1") (pintype "passive"))
    )
    (net (code "49") (name "Net-(D28-A)") (class "Default")
      (node (ref "D28") (pin "2") (pinfunction "A_2") (pintype "passive"))
      (node (ref "S28") (pin "1") (pinfunction "1_1") (pintype "passive"))
    )
    (net (code "50") (name "Net-(D29-A)") (class "Default")
      (node (ref "D29") (pin "2") (pinfunction "A_2") (pintype "passive"))
      (node (ref "S29") (pin "1") (pinfunction "1_1") (pintype "passive"))
    )
    (net (code "51") (name "Net-(D30-A)") (class "Default")
      (node (ref "D30") (pin "2") (pinfunction "A_2") (pintype "passive"))
      (node (ref "S30") (pin "1") (pinfunction "1_1") (pintype "passive"))
    )
    (net (code "52") (name "Net-(D31-A)") (class "Default")
      (node (ref "D31") (pin "2") (pinfunction "A_2") (pintype "passive"))
      (node (ref "S31") (pin "1") (pinfunction "1_1") (pintype "passive"))
    )
    (net (code "53") (name "Net-(D32-A)") (class "Default")
      (node (ref "D32") (pin "2") (pinfunction "A_2") (pintype "passive"))
      (node (ref "S32") (pin "1") (pinfunction "1_1") (pintype "passive"))
    )
    (net (code "54") (name "Net-(D33-A)") (class "Default")
      (node (ref "D33") (pin "2") (pinfunction "A_2") (pintype "passive"))
      (node (ref "S33") (pin "1") (pinfunction "1_1") (pintype "passive"))
    )
    (net (code "55") (name "Net-(D34-A)") (class "Default")
      (node (ref "D34") (pin "2") (pinfunction "A_2") (pintype "passive"))
      (node (ref "S34") (pin "1") (pinfunction "1_1") (pintype "passive"))
    )
    (net (code "56") (name "Net-(D35-A)") (class "Default")
      (node (ref "D35") (pin "2") (pinfunction "A_2") (pintype "passive"))
      (node (ref "S35") (pin "1") (pinfunction "1_1") (pintype "passive"))
    )
    (net (code "57") (name "Net-(D36-A)") (class "Default")
      (node (ref "D36") (pin "2") (pinfunction "A_2") (pintype "passive"))
      (node (ref "S36") (pin "1") (pinfunction "1_1") (pintype "passive"))
    )
    (net (code "58") (name "Net-(D37-A)") (class "Default")
      (node (ref "D37") (pin "2") (pinfunction "A_2") (pintype "passive"))
      (node (ref "S37") (pin "1") (pinfunction "1_1") (pintype "passive"))
    )
    (net (code "59") (name "Net-(D38-A)") (class "Default")
      (node (ref "D38") (pin "2") (pinfunction "A_2") (pintype "passive"))
      (node (ref "S38") (pin "1") (pinfunction "1_1") (pintype "passive"))
    )
    (net (code "60") (name "Net-(D39-A)") (class "Default")
      (node (ref "D39") (pin "2") (pinfunction "A_2") (pintype "passive"))
      (node (ref "S39") (pin "1") (pinfunction "1_1") (pintype "passive"))
    )
    (net (code "61") (name "Net-(D40-A)") (class "Default")
      (node (ref "D40") (pin "2") (pinfunction "A_2") (pintype "passive"))
      (node (ref "S40") (pin "1") (pinfunction "1_1") (pintype "passive"))
    )
    (net (code "62") (name "Net-(D41-A)") (class "Default")
      (node (ref "D41") (pin "2") (pinfunction "A_2") (pintype "passive"))
      (node (ref "S41") (pin "1") (pinfunction "1_1") (pintype "passive"))
    )
    (net (code "63") (name "Net-(D42-A)") (class "Default")
      (node (ref "D42") (pin "2") (pinfunction "A_2") (pintype "passive"))
      (node (ref "S42") (pin "1") (pinfunction "1_1") (pintype "passive"))
    )
    (net (code "64") (name "Net-(D43-A)") (class "Default")
      (node (ref "D43") (pin "2") (pinfunction "A_2") (pintype "passive"))
      (node (ref "S43") (pin "1") (pinfunction "1_1") (pintype "passive"))
    )
    (net (code "65") (name "Net-(D44-A)") (class "Default")
      (node (ref "D44") (pin "2") (pinfunction "A_2") (pintype "passive"))
      (node (ref "S44") (pin "1") (pinfunction "1_1") (pintype "passive"))
    )
    (net (code "66") (name "Net-(D45-A)") (class "Default")
      (node (ref "D45") (pin "2") (pinfunction "A_2") (pintype "passive"))
      (node (ref "S45") (pin "1") (pinfunction "1_1") (pintype "passive"))
    )
    (net (code "67") (name "Net-(D46-A)") (class "Default")
      (node (ref "D46") (pin "2") (pinfunction "A_2") (pintype "passive"))
      (node (ref "S46") (pin "1") (pinfunction "1_1") (pintype "passive"))
    )
    (net (code "68") (name "Net-(D47-A)") (class "Default")
      (node (ref "D47") (pin "2") (pinfunction "A_2") (pintype "passive"))
      (node (ref "S47") (pin "1") (pinfunction "1_1") (pintype "passive"))
    )
    (net (code "69") (name "Net-(D48-A)") (class "Default")
      (node (ref "D48") (pin "2") (pinfunction "A_2") (pintype "passive"))
      (node (ref "S48") (pin "1") (pinfunction "1_1") (pintype "passive"))
    )
    (net (code "70") (name "Net-(D49-A)") (class "Default")
      (node (ref "D49") (pin "2") (pinfunction "A_2") (pintype "passive"))
      (node (ref "S49") (pin "1") (pinfunction "1_1") (pintype "passive"))
    )
    (net (code "71") (name "Net-(D50-A)") (class "Default")
      (node (ref "D50") (pin "2") (pinfunction "A_2") (pintype "passive"))
      (node (ref "S50") (pin "1") (pinfunction "1_1") (pintype "passive"))
    )
    (net (code "72") (name "Net-(D51-A)") (class "Default")
      (node (ref "D51") (pin "2") (pinfunction "A_2") (pintype "passive"))
      (node (ref "S51") (pin "1") (pinfunction "1_1") (pintype "passive"))
    )
    (net (code "73") (name "Net-(D52-A)") (class "Default")
      (node (ref "D52") (pin "2") (pinfunction "A_2") (pintype "passive"))
      (node (ref "S52") (pin "1") (pinfunction "1_1") (pintype "passive"))
    )
    (net (code "74") (name "Net-(D53-A)") (class "Default")
      (node (ref "D53") (pin "2") (pinfunction "A_2") (pintype "passive"))
      (node (ref "S53") (pin "1") (pinfunction "1_1") (pintype "passive"))
    )
    (net (code "75") (name "Net-(D54-A)") (class "Default")
      (node (ref "D54") (pin "2") (pinfunction "A_2") (pintype "passive"))
      (node (ref "S54") (pin "1") (pinfunction "1_1") (pintype "passive"))
    )
    (net (code "76") (name "Net-(D55-A)") (class "Default")
      (node (ref "D55") (pin "2") (pinfunction "A_2") (pintype "passive"))
      (node (ref "S55") (pin "1") (pinfunction "1_1") (pintype "passive"))
    )
    (net (code "77") (name "Net-(D56-A)") (class "Default")
      (node (ref "D56") (pin "2") (pinfunction "A_2") (pintype "passive"))
      (node (ref "S56") (pin "1") (pinfunction "1_1") (pintype "passive"))
    )
    (net (code "78") (name "Net-(D57-A)") (class "Default")
      (node (ref "D57") (pin "2") (pinfunction "A_2") (pintype "passive"))
      (node (ref "S57") (pin "1") (pinfunction "1_1") (pintype "passive"))
    )
    (net (code "79") (name "Net-(D58-A)") (class "Default")
      (node (ref "D58") (pin "2") (pinfunction "A_2") (pintype "passive"))
      (node (ref "S58") (pin "1") (pinfunction "1_1") (pintype "passive"))
    )
    (net (code "80") (name "Net-(D59-A)") (class "Default")
      (node (ref "D59") (pin "2") (pinfunction "A_2") (pintype "passive"))
      (node (ref "S59") (pin "1") (pinfunction "1_1") (pintype "passive"))
    )
    (net (code "81") (name "Net-(D60-A)") (class "Default")
      (node (ref "D60") (pin "2") (pinfunction "A_2") (pintype "passive"))
      (node (ref "S60") (pin "1") (pinfunction "1_1") (pintype "passive"))
    )
    (net (code "82") (name "Net-(D61-A)") (class "Default")
      (node (ref "D61") (pin "2") (pinfunction "A_2") (pintype "passive"))
      (node (ref "S61") (pin "1") (pinfunction "1_1") (pintype "passive"))
    )
  )
)
